# ADC.net
KiCad netlist of a schematic drawn in Altium Designer
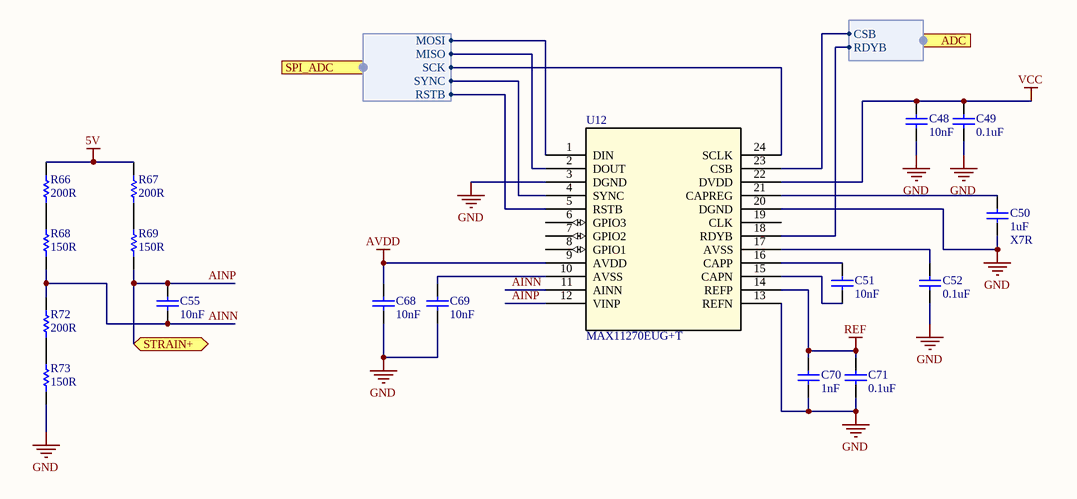
[diagram p0: ADC.SchDoc]

(export (version "E")
  (design (tool "Eeschema 10.0.6"))
  (components
    (comp (ref "C48")
      (value "10nF")
      (footprint "C0603[1608X92]")
      (description "10nF 6.3V 10% 0603 (1608 Metric)")
      (fields (field (name "PARTNUMBER") "GRM188R70J103KA01D") (field (name "MANUFACTURER") "Murata"))
      (libsource (lib "Capacitors") (part "CAP_10nF_6.3V_0603_10%"))
    )
    (comp (ref "C49")
      (value "0.1uF")
      (footprint "C0603[1608X92]")
      (description "0.1uF 6.3V 10% 0603 (1608 Metric)")
      (fields (field (name "PARTNUMBER") "GRM188R70J104KA01D") (field (name "MANUFACTURER") "Murata"))
      (libsource (lib "Capacitors") (part "CAP_0.1uF_6.3V_0603_10%"))
    )
    (comp (ref "C50")
      (value "1uF")
      (footprint "C0603[1608X92]")
      (description "1uF 16V 10% 0603 X7R (1608 Metric)")
      (fields
        (field (name "PARTNUMBER") "GCJ188R71E105KA01D")
        (field (name "MANUFACTURER") "Murata")
        (field (name "TEMPERATURECOEFFICIENT") "X7R")
      )
      (libsource (lib "Capacitors") (part "CAP_1uF_16V_0603_10%_X7R"))
    )
    (comp (ref "C51")
      (value "10nF")
      (footprint "C0603[1608X92]")
      (description "10nF 6.3V 10% 0603 (1608 Metric)")
      (fields (field (name "PARTNUMBER") "GRM188R70J103KA01D") (field (name "MANUFACTURER") "Murata"))
      (libsource (lib "Capacitors") (part "CAP_10nF_6.3V_0603_10%"))
    )
    (comp (ref "C52")
      (value "0.1uF")
      (footprint "C0603[1608X92]")
      (description "0.1uF 6.3V 10% 0603 (1608 Metric)")
      (fields (field (name "PARTNUMBER") "GRM188R70J104KA01D") (field (name "MANUFACTURER") "Murata"))
      (libsource (lib "Capacitors") (part "CAP_0.1uF_6.3V_0603_10%"))
    )
    (comp (ref "C55")
      (value "10nF")
      (footprint "C0603[1608X92]")
      (description "10nF 6.3V 10% 0603 (1608 Metric)")
      (fields (field (name "PARTNUMBER") "GRM188R70J103KA01D") (field (name "MANUFACTURER") "Murata"))
      (libsource (lib "Capacitors") (part "CAP_10nF_6.3V_0603_10%"))
    )
    (comp (ref "C68")
      (value "10nF")
      (footprint "C0603[1608X92]")
      (description "10nF 6.3V 10% 0603 (1608 Metric)")
      (fields (field (name "PARTNUMBER") "GRM188R70J103KA01D") (field (name "MANUFACTURER") "Murata"))
      (libsource (lib "Capacitors") (part "CAP_10nF_6.3V_0603_10%"))
    )
    (comp (ref "C69")
      (value "10nF")
      (footprint "C0603[1608X92]")
      (description "10nF 6.3V 10% 0603 (1608 Metric)")
      (fields (field (name "PARTNUMBER") "GRM188R70J103KA01D") (field (name "MANUFACTURER") "Murata"))
      (libsource (lib "Capacitors") (part "CAP_10nF_6.3V_0603_10%"))
    )
    (comp (ref "C70")
      (value "1nF")
      (footprint "C0603[1608X92]")
      (description "1nF 6.3V 5% 0603 (1608 Metric)")
      (fields (field (name "PARTNUMBER") "GRM1885C1H102JA01D") (field (name "MANUFACTURER") "Murata"))
      (libsource (lib "Capacitors") (part "CAP_1nF_6.3V_0603_5%"))
    )
    (comp (ref "C71")
      (value "0.1uF")
      (footprint "C0603[1608X92]")
      (description "0.1uF 6.3V 10% 0603 (1608 Metric)")
      (fields (field (name "PARTNUMBER") "GRM188R70J104KA01D") (field (name "MANUFACTURER") "Murata"))
      (libsource (lib "Capacitors") (part "CAP_0.1uF_6.3V_0603_10%"))
    )
    (comp (ref "R66")
      (value "200R")
      (footprint "R0603[1608]")
      (description "200R 0.25W 1% 0603 (1005 Metric)")
      (fields (field (name "MANUFACTURER") "Vishay / Dale") (field (name "PARTNUMBER") "CRCW0603200RFKEAHP"))
      (libsource (lib "Resistors") (part "RES_200R_0603_1%"))
    )
    (comp (ref "R67")
      (value "200R")
      (footprint "R0603[1608]")
      (description "200R 0.25W 1% 0603 (1005 Metric)")
      (fields (field (name "MANUFACTURER") "Vishay / Dale") (field (name "PARTNUMBER") "CRCW0603200RFKEAHP"))
      (libsource (lib "Resistors") (part "RES_200R_0603_1%"))
    )
    (comp (ref "R68")
      (value "150R")
      (footprint "R0603[1608]")
      (description "150R 0.25W 1% 0603 (1005 Metric)")
      (fields (field (name "MANUFACTURER") "Vishay / Dale") (field (name "PARTNUMBER") "CRCW0603150RFKEAHP"))
      (libsource (lib "Resistors") (part "RES_150R_0603_1%"))
    )
    (comp (ref "R69")
      (value "150R")
      (footprint "R0603[1608]")
      (description "150R 0.25W 1% 0603 (1005 Metric)")
      (fields (field (name "MANUFACTURER") "Vishay / Dale") (field (name "PARTNUMBER") "CRCW0603150RFKEAHP"))
      (libsource (lib "Resistors") (part "RES_150R_0603_1%"))
    )
    (comp (ref "R72")
      (value "200R")
      (footprint "R0603[1608]")
      (description "200R 0.25W 1% 0603 (1005 Metric)")
      (fields (field (name "MANUFACTURER") "Vishay / Dale") (field (name "PARTNUMBER") "CRCW0603200RFKEAHP"))
      (libsource (lib "Resistors") (part "RES_200R_0603_1%"))
    )
    (comp (ref "R73")
      (value "150R")
      (footprint "R0603[1608]")
      (description "150R 0.25W 1% 0603 (1005 Metric)")
      (fields (field (name "MANUFACTURER") "Vishay / Dale") (field (name "PARTNUMBER") "CRCW0603150RFKEAHP"))
      (libsource (lib "Resistors") (part "RES_150R_0603_1%"))
    )
    (comp (ref "U12")
      (value "MAX11270EUG+T")
      (footprint "21-0066J_24")
      (description "Imported")
      (fields (field (name "PARTNUMBER") "MAX111270EUG+T") (field (name "MANUFACTURER") "Maxim"))
      (libsource (lib "General_Component") (part "MAX11270EUG+T"))
    )
  )
  (nets
    (net (code "3") (name "/AINN") (class "Default")
      (node (ref "C55") (pin "1") (pinfunction "1_1") (pintype "passive"))
      (node (ref "R68") (pin "1") (pinfunction "1_1") (pintype "passive"))
      (node (ref "R72") (pin "2") (pinfunction "2_2") (pintype "passive"))
      (node (ref "U12") (pin "11") (pinfunction "AINN_11") (pintype "passive"))
    )
    (net (code "4") (name "/AINP") (class "Default")
      (node (ref "C55") (pin "2") (pinfunction "2_2") (pintype "passive"))
      (node (ref "R69") (pin "1") (pinfunction "1_1") (pintype "passive"))
      (node (ref "U12") (pin "12") (pinfunction "VINP_12") (pintype "passive"))
    )
    (net (code "5") (name "/CSB") (class "Default")
      (node (ref "U12") (pin "23") (pinfunction "CSB_23") (pintype "passive"))
    )
    (net (code "6") (name "/MISO") (class "Default")
      (node (ref "U12") (pin "2") (pinfunction "DOUT_2") (pintype "passive"))
    )
    (net (code "7") (name "/MOSI") (class "Default")
      (node (ref "U12") (pin "1") (pinfunction "DIN_1") (pintype "passive"))
    )
    (net (code "8") (name "/RDYB") (class "Default")
      (node (ref "U12") (pin "18") (pinfunction "RDYB_18") (pintype "passive"))
    )
    (net (code "9") (name "/RSTB") (class "Default")
      (node (ref "U12") (pin "5") (pinfunction "RSTB_5") (pintype "passive"))
    )
    (net (code "10") (name "/SCK") (class "Default")
      (node (ref "U12") (pin "24") (pinfunction "SCLK_24") (pintype "passive"))
    )
    (net (code "11") (name "/SYNC") (class "Default")
      (node (ref "U12") (pin "4") (pinfunction "SYNC_4") (pintype "passive"))
    )
    (net (code "14") (name "5V") (class "Default")
      (node (ref "R66") (pin "2") (pinfunction "2_2") (pintype "passive"))
      (node (ref "R67") (pin "2") (pinfunction "2_2") (pintype "passive"))
    )
    (net (code "15") (name "AVDD") (class "Default")
      (node (ref "C68") (pin "2") (pinfunction "2_2") (pintype "passive"))
      (node (ref "U12") (pin "9") (pinfunction "AVDD_9") (pintype "power_in"))
    )
    (net (code "16") (name "GND") (class "Default")
      (node (ref "C48") (pin "1") (pinfunction "1_1") (pintype "passive"))
      (node (ref "C49") (pin "1") (pinfunction "1_1") (pintype "passive"))
      (node (ref "C50") (pin "1") (pinfunction "1_1") (pintype "passive"))
      (node (ref "C52") (pin "1") (pinfunction "1_1") (pintype "passive"))
      (node (ref "C68") (pin "1") (pinfunction "1_1") (pintype "passive"))
      (node (ref "C69") (pin "1") (pinfunction "1_1") (pintype "passive"))
      (node (ref "C70") (pin "1") (pinfunction "1_1") (pintype "passive"))
      (node (ref "C71") (pin "1") (pinfunction "1_1") (pintype "passive"))
      (node (ref "R73") (pin "1") (pinfunction "1_1") (pintype "passive"))
      (node (ref "U12") (pin "13") (pinfunction "REFN_13") (pintype "passive"))
      (node (ref "U12") (pin "20") (pinfunction "DGND_20") (pintype "power_in"))
      (node (ref "U12") (pin "3") (pinfunction "DGND_3") (pintype "power_in"))
    )
    (net (code "17") (name "Net-(C52-Pad2)") (class "Default")
      (node (ref "C52") (pin "2") (pinfunction "2_2") (pintype "passive"))
      (node (ref "U12") (pin "17") (pinfunction "AVSS_17") (pintype "power_in"))
    )
    (net (code "18") (name "Net-(C69-Pad2)") (class "Default")
      (node (ref "C69") (pin "2") (pinfunction "2_2") (pintype "passive"))
      (node (ref "U12") (pin "10") (pinfunction "AVSS_10") (pintype "power_in"))
    )
    (net (code "19") (name "Net-(R66-Pad1)") (class "Default")
      (node (ref "R66") (pin "1") (pinfunction "1_1") (pintype "passive"))
      (node (ref "R68") (pin "2") (pinfunction "2_2") (pintype "passive"))
    )
    (net (code "20") (name "Net-(R67-Pad1)") (class "Default")
      (node (ref "R67") (pin "1") (pinfunction "1_1") (pintype "passive"))
      (node (ref "R69") (pin "2") (pinfunction "2_2") (pintype "passive"))
    )
    (net (code "21") (name "Net-(R72-Pad1)") (class "Default")
      (node (ref "R72") (pin "1") (pinfunction "1_1") (pintype "passive"))
      (node (ref "R73") (pin "2") (pinfunction "2_2") (pintype "passive"))
    )
    (net (code "22") (name "Net-(U12-CAPN)") (class "Default")
      (node (ref "C51") (pin "1") (pinfunction "1_1") (pintype "passive"))
      (node (ref "U12") (pin "15") (pinfunction "CAPN_15") (pintype "passive"))
    )
    (net (code "23") (name "Net-(U12-CAPP)") (class "Default")
      (node (ref "C51") (pin "2") (pinfunction "2_2") (pintype "passive"))
      (node (ref "U12") (pin "16") (pinfunction "CAPP_16") (pintype "passive"))
    )
    (net (code "24") (name "Net-(U12-CAPREG)") (class "Default")
      (node (ref "C50") (pin "2") (pinfunction "2_2") (pintype "passive"))
      (node (ref "U12") (pin "21") (pinfunction "CAPREG_21") (pintype "power_in"))
    )
    (net (code "25") (name "REF") (class "Default")
      (node (ref "C70") (pin "2") (pinfunction "2_2") (pintype "passive"))
      (node (ref "C71") (pin "2") (pinfunction "2_2") (pintype "passive"))
      (node (ref "U12") (pin "14") (pinfunction "REFP_14") (pintype "passive"))
    )
    (net (code "26") (name "VCC") (class "Default")
      (node (ref "C48") (pin "2") (pinfunction "2_2") (pintype "passive"))
      (node (ref "C49") (pin "2") (pinfunction "2_2") (pintype "passive"))
      (node (ref "U12") (pin "22") (pinfunction "DVDD_22") (pintype "power_in"))
    )
    (net (code "27") (name "unconnected-(U12-CLK-Pad19)") (class "Default")
      (node (ref "U12") (pin "19") (pinfunction "CLK_19") (pintype "passive"))
    )
    (net (code "28") (name "unconnected-(U12-GPIO1-Pad8)") (class "Default")
      (node (ref "U12") (pin "8") (pinfunction "GPIO1_8") (pintype "bidirectional"))
    )
    (net (code "29") (name "unconnected-(U12-GPIO2-Pad7)") (class "Default")
      (node (ref "U12") (pin "7") (pinfunction "GPIO2_7") (pintype "bidirectional"))
    )
    (net (code "30") (name "unconnected-(U12-GPIO3-Pad6)") (class "Default")
      (node (ref "U12") (pin "6") (pinfunction "GPIO3_6") (pintype "bidirectional"))
    )
  )
)
